# main.net
KiCad netlist of a schematic drawn in EAGLE
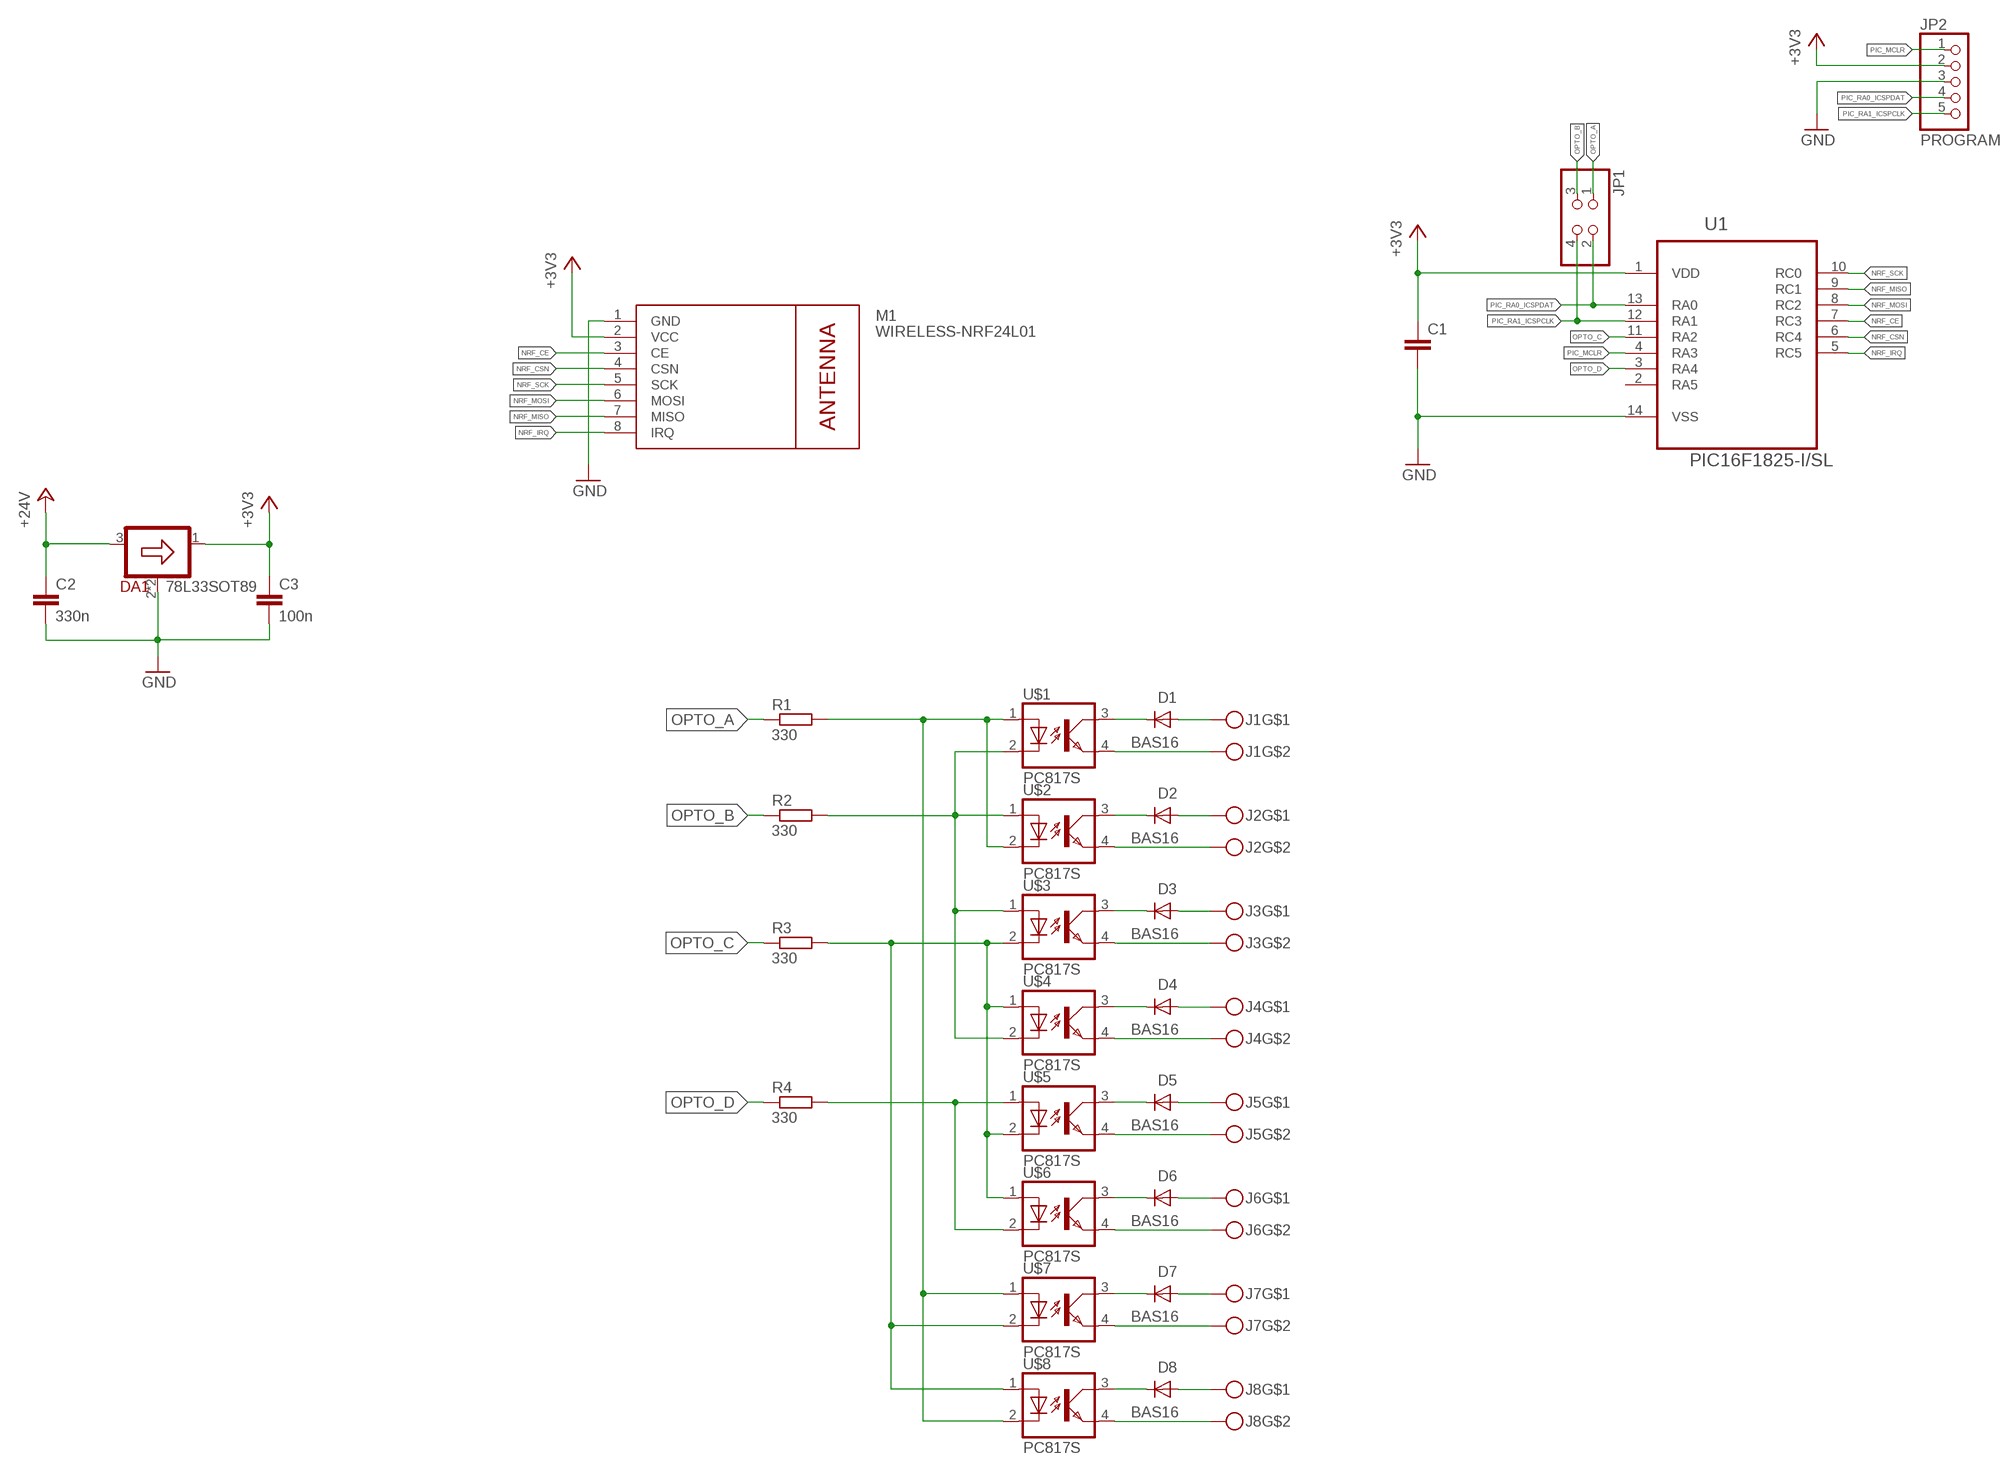
[diagram p0: schematic, sheet 1]

(export (version "E")
  (design (tool "Eeschema 10.0.6"))
  (components
    (comp (ref "C1")
      (value "C-EUC1206")
      (footprint "eagle-import:C1206")
      (libsource (lib "eagle-import") (part "C-EUC1206"))
    )
    (comp (ref "C2")
      (value "330n")
      (footprint "eagle-import:C1206")
      (libsource (lib "eagle-import") (part "C-EUC1206"))
    )
    (comp (ref "C3")
      (value "100n")
      (footprint "eagle-import:C1206")
      (libsource (lib "eagle-import") (part "C-EUC1206"))
    )
    (comp (ref "D1")
      (value "BAS16")
      (footprint "eagle-import:SOT23")
      (libsource (lib "eagle-import") (part "BAS16"))
    )
    (comp (ref "D2")
      (value "BAS16")
      (footprint "eagle-import:SOT23")
      (libsource (lib "eagle-import") (part "BAS16"))
    )
    (comp (ref "D3")
      (value "BAS16")
      (footprint "eagle-import:SOT23")
      (libsource (lib "eagle-import") (part "BAS16"))
    )
    (comp (ref "D4")
      (value "BAS16")
      (footprint "eagle-import:SOT23")
      (libsource (lib "eagle-import") (part "BAS16"))
    )
    (comp (ref "D5")
      (value "BAS16")
      (footprint "eagle-import:SOT23")
      (libsource (lib "eagle-import") (part "BAS16"))
    )
    (comp (ref "D6")
      (value "BAS16")
      (footprint "eagle-import:SOT23")
      (libsource (lib "eagle-import") (part "BAS16"))
    )
    (comp (ref "D7")
      (value "BAS16")
      (footprint "eagle-import:SOT23")
      (libsource (lib "eagle-import") (part "BAS16"))
    )
    (comp (ref "D8")
      (value "BAS16")
      (footprint "eagle-import:SOT23")
      (libsource (lib "eagle-import") (part "BAS16"))
    )
    (comp (ref "DA1")
      (value "78L33SOT89")
      (footprint "eagle-import:SOT89")
      (libsource (lib "eagle-import") (part "78L33SOT89"))
    )
    (comp (ref "J1")
      (value "SCREW-TERMINAL-2PIN")
      (footprint "eagle-import:PITCH4.3-PIN2")
      (libsource (lib "eagle-import") (part "SCREW-TERMINAL-2PIN"))
    )
    (comp (ref "J2")
      (value "SCREW-TERMINAL-2PIN")
      (footprint "eagle-import:PITCH4.3-PIN2")
      (libsource (lib "eagle-import") (part "SCREW-TERMINAL-2PIN"))
    )
    (comp (ref "J3")
      (value "SCREW-TERMINAL-2PIN")
      (footprint "eagle-import:PITCH4.3-PIN2")
      (libsource (lib "eagle-import") (part "SCREW-TERMINAL-2PIN"))
    )
    (comp (ref "J4")
      (value "SCREW-TERMINAL-2PIN")
      (footprint "eagle-import:PITCH4.3-PIN2")
      (libsource (lib "eagle-import") (part "SCREW-TERMINAL-2PIN"))
    )
    (comp (ref "J5")
      (value "SCREW-TERMINAL-2PIN")
      (footprint "eagle-import:PITCH4.3-PIN2")
      (libsource (lib "eagle-import") (part "SCREW-TERMINAL-2PIN"))
    )
    (comp (ref "J6")
      (value "SCREW-TERMINAL-2PIN")
      (footprint "eagle-import:PITCH4.3-PIN2")
      (libsource (lib "eagle-import") (part "SCREW-TERMINAL-2PIN"))
    )
    (comp (ref "J7")
      (value "SCREW-TERMINAL-2PIN")
      (footprint "eagle-import:PITCH4.3-PIN2")
      (libsource (lib "eagle-import") (part "SCREW-TERMINAL-2PIN"))
    )
    (comp (ref "J8")
      (value "SCREW-TERMINAL-2PIN")
      (footprint "eagle-import:PITCH4.3-PIN2")
      (libsource (lib "eagle-import") (part "SCREW-TERMINAL-2PIN"))
    )
    (comp (ref "JP1")
      (value "PINHD-2X2")
      (footprint "eagle-import:2X02")
      (libsource (lib "eagle-import") (part "PINHD-2X2"))
    )
    (comp (ref "JP2")
      (value "PROGRAM")
      (footprint "eagle-import:1X05")
      (libsource (lib "eagle-import") (part "PINHD-1X5"))
    )
    (comp (ref "M1")
      (value "WIRELESS-NRF24L01")
      (footprint "eagle-import:WIRELESS-NRF24L01")
      (libsource (lib "eagle-import") (part "WIRELESS-NRF24L01"))
    )
    (comp (ref "R1")
      (value "330")
      (footprint "eagle-import:R1206")
      (libsource (lib "eagle-import") (part "R-EU_R1206"))
    )
    (comp (ref "R2")
      (value "330")
      (footprint "eagle-import:R1206")
      (libsource (lib "eagle-import") (part "R-EU_R1206"))
    )
    (comp (ref "R3")
      (value "330")
      (footprint "eagle-import:R1206")
      (libsource (lib "eagle-import") (part "R-EU_R1206"))
    )
    (comp (ref "R4")
      (value "330")
      (footprint "eagle-import:R1206")
      (libsource (lib "eagle-import") (part "R-EU_R1206"))
    )
    (comp (ref "U$1")
      (value "PC817S")
      (footprint "eagle-import:SMD4-7")
      (libsource (lib "eagle-import") (part "PC817S"))
    )
    (comp (ref "U$2")
      (value "PC817S")
      (footprint "eagle-import:SMD4-7")
      (libsource (lib "eagle-import") (part "PC817S"))
    )
    (comp (ref "U$3")
      (value "PC817S")
      (footprint "eagle-import:SMD4-7")
      (libsource (lib "eagle-import") (part "PC817S"))
    )
    (comp (ref "U$4")
      (value "PC817S")
      (footprint "eagle-import:SMD4-7")
      (libsource (lib "eagle-import") (part "PC817S"))
    )
    (comp (ref "U$5")
      (value "PC817S")
      (footprint "eagle-import:SMD4-7")
      (libsource (lib "eagle-import") (part "PC817S"))
    )
    (comp (ref "U$6")
      (value "PC817S")
      (footprint "eagle-import:SMD4-7")
      (libsource (lib "eagle-import") (part "PC817S"))
    )
    (comp (ref "U$7")
      (value "PC817S")
      (footprint "eagle-import:SMD4-7")
      (libsource (lib "eagle-import") (part "PC817S"))
    )
    (comp (ref "U$8")
      (value "PC817S")
      (footprint "eagle-import:SMD4-7")
      (libsource (lib "eagle-import") (part "PC817S"))
    )
    (comp (ref "U1")
      (value "PIC16F1825-I/SL")
      (footprint "eagle-import:SOIC127P600X175-14N")
      (libsource (lib "eagle-import") (part "PIC16F1825-I/SL"))
    )
  )
  (nets
    (net (code "1") (name "+3V3") (class "Default")
      (node (ref "C1") (pin "1") (pinfunction "1_1") (pintype "passive"))
      (node (ref "C3") (pin "1") (pinfunction "1_1") (pintype "passive"))
      (node (ref "DA1") (pin "1") (pinfunction "OUT_1") (pintype "power_in"))
      (node (ref "JP2") (pin "2") (pinfunction "2_2") (pintype "passive"))
      (node (ref "M1") (pin "2") (pinfunction "VCC_2") (pintype "power_in"))
      (node (ref "U1") (pin "1") (pinfunction "VDD_1") (pintype "power_in"))
    )
    (net (code "2") (name "+24V") (class "Default")
      (node (ref "C2") (pin "1") (pinfunction "1_1") (pintype "passive"))
      (node (ref "DA1") (pin "3") (pinfunction "IN_3") (pintype "power_in"))
    )
    (net (code "3") (name "GND") (class "Default")
      (node (ref "C1") (pin "2") (pinfunction "2_2") (pintype "passive"))
      (node (ref "C2") (pin "2") (pinfunction "2_2") (pintype "passive"))
      (node (ref "C3") (pin "2") (pinfunction "2_2") (pintype "passive"))
      (node (ref "DA1") (pin "2") (pinfunction "GND_2") (pintype "power_in"))
      (node (ref "DA1") (pin "2@1") (pinfunction "GND_2@1") (pintype "power_in"))
      (node (ref "JP2") (pin "3") (pinfunction "3_3") (pintype "passive"))
      (node (ref "M1") (pin "1") (pinfunction "GND_1") (pintype "power_in"))
      (node (ref "U1") (pin "14") (pinfunction "VSS_14") (pintype "passive"))
    )
    (net (code "4") (name "NRF_CE") (class "Default")
      (node (ref "M1") (pin "3") (pinfunction "CE_3") (pintype "bidirectional"))
      (node (ref "U1") (pin "7") (pinfunction "RC3_7") (pintype "bidirectional"))
    )
    (net (code "5") (name "NRF_CSN") (class "Default")
      (node (ref "M1") (pin "4") (pinfunction "CSN_4") (pintype "bidirectional"))
      (node (ref "U1") (pin "6") (pinfunction "RC4_6") (pintype "bidirectional"))
    )
    (net (code "6") (name "NRF_IRQ") (class "Default")
      (node (ref "M1") (pin "8") (pinfunction "IRQ_8") (pintype "bidirectional"))
      (node (ref "U1") (pin "5") (pinfunction "RC5_5") (pintype "bidirectional"))
    )
    (net (code "7") (name "NRF_MISO") (class "Default")
      (node (ref "M1") (pin "7") (pinfunction "MISO_7") (pintype "bidirectional"))
      (node (ref "U1") (pin "9") (pinfunction "RC1_9") (pintype "bidirectional"))
    )
    (net (code "8") (name "NRF_MOSI") (class "Default")
      (node (ref "M1") (pin "6") (pinfunction "MOSI_6") (pintype "bidirectional"))
      (node (ref "U1") (pin "8") (pinfunction "RC2_8") (pintype "bidirectional"))
    )
    (net (code "9") (name "NRF_SCK") (class "Default")
      (node (ref "M1") (pin "5") (pinfunction "SCK_5") (pintype "bidirectional"))
      (node (ref "U1") (pin "10") (pinfunction "RC0_10") (pintype "bidirectional"))
    )
    (net (code "10") (name "Net-(D1-A)") (class "Default")
      (node (ref "D1") (pin "1") (pinfunction "A_1") (pintype "passive"))
      (node (ref "J1") (pin "1") (pinfunction "KL_1") (pintype "passive"))
    )
    (net (code "11") (name "Net-(D1-K)") (class "Default")
      (node (ref "D1") (pin "3") (pinfunction "K_3") (pintype "passive"))
      (node (ref "U$1") (pin "3") (pinfunction "COL_3") (pintype "passive"))
    )
    (net (code "12") (name "Net-(D2-A)") (class "Default")
      (node (ref "D2") (pin "1") (pinfunction "A_1") (pintype "passive"))
      (node (ref "J2") (pin "1") (pinfunction "KL_1") (pintype "passive"))
    )
    (net (code "13") (name "Net-(D2-K)") (class "Default")
      (node (ref "D2") (pin "3") (pinfunction "K_3") (pintype "passive"))
      (node (ref "U$2") (pin "3") (pinfunction "COL_3") (pintype "passive"))
    )
    (net (code "14") (name "Net-(D3-A)") (class "Default")
      (node (ref "D3") (pin "1") (pinfunction "A_1") (pintype "passive"))
      (node (ref "J3") (pin "1") (pinfunction "KL_1") (pintype "passive"))
    )
    (net (code "15") (name "Net-(D3-K)") (class "Default")
      (node (ref "D3") (pin "3") (pinfunction "K_3") (pintype "passive"))
      (node (ref "U$3") (pin "3") (pinfunction "COL_3") (pintype "passive"))
    )
    (net (code "16") (name "Net-(D4-A)") (class "Default")
      (node (ref "D4") (pin "1") (pinfunction "A_1") (pintype "passive"))
      (node (ref "J4") (pin "1") (pinfunction "KL_1") (pintype "passive"))
    )
    (net (code "17") (name "Net-(D4-K)") (class "Default")
      (node (ref "D4") (pin "3") (pinfunction "K_3") (pintype "passive"))
      (node (ref "U$4") (pin "3") (pinfunction "COL_3") (pintype "passive"))
    )
    (net (code "18") (name "Net-(D5-A)") (class "Default")
      (node (ref "D5") (pin "1") (pinfunction "A_1") (pintype "passive"))
      (node (ref "J5") (pin "1") (pinfunction "KL_1") (pintype "passive"))
    )
    (net (code "19") (name "Net-(D5-K)") (class "Default")
      (node (ref "D5") (pin "3") (pinfunction "K_3") (pintype "passive"))
      (node (ref "U$5") (pin "3") (pinfunction "COL_3") (pintype "passive"))
    )
    (net (code "20") (name "Net-(D6-A)") (class "Default")
      (node (ref "D6") (pin "1") (pinfunction "A_1") (pintype "passive"))
      (node (ref "J6") (pin "1") (pinfunction "KL_1") (pintype "passive"))
    )
    (net (code "21") (name "Net-(D6-K)") (class "Default")
      (node (ref "D6") (pin "3") (pinfunction "K_3") (pintype "passive"))
      (node (ref "U$6") (pin "3") (pinfunction "COL_3") (pintype "passive"))
    )
    (net (code "22") (name "Net-(D7-A)") (class "Default")
      (node (ref "D7") (pin "1") (pinfunction "A_1") (pintype "passive"))
      (node (ref "J7") (pin "1") (pinfunction "KL_1") (pintype "passive"))
    )
    (net (code "23") (name "Net-(D7-K)") (class "Default")
      (node (ref "D7") (pin "3") (pinfunction "K_3") (pintype "passive"))
      (node (ref "U$7") (pin "3") (pinfunction "COL_3") (pintype "passive"))
    )
    (net (code "24") (name "Net-(D8-A)") (class "Default")
      (node (ref "D8") (pin "1") (pinfunction "A_1") (pintype "passive"))
      (node (ref "J8") (pin "1") (pinfunction "KL_1") (pintype "passive"))
    )
    (net (code "25") (name "Net-(D8-K)") (class "Default")
      (node (ref "D8") (pin "3") (pinfunction "K_3") (pintype "passive"))
      (node (ref "U$8") (pin "3") (pinfunction "COL_3") (pintype "passive"))
    )
    (net (code "26") (name "Net-(J1B-KL)") (class "Default")
      (node (ref "J1") (pin "2") (pinfunction "KL_2") (pintype "passive"))
      (node (ref "U$1") (pin "4") (pinfunction "EMIT_4") (pintype "passive"))
    )
    (net (code "27") (name "Net-(J2B-KL)") (class "Default")
      (node (ref "J2") (pin "2") (pinfunction "KL_2") (pintype "passive"))
      (node (ref "U$2") (pin "4") (pinfunction "EMIT_4") (pintype "passive"))
    )
    (net (code "28") (name "Net-(J3B-KL)") (class "Default")
      (node (ref "J3") (pin "2") (pinfunction "KL_2") (pintype "passive"))
      (node (ref "U$3") (pin "4") (pinfunction "EMIT_4") (pintype "passive"))
    )
    (net (code "29") (name "Net-(J4B-KL)") (class "Default")
      (node (ref "J4") (pin "2") (pinfunction "KL_2") (pintype "passive"))
      (node (ref "U$4") (pin "4") (pinfunction "EMIT_4") (pintype "passive"))
    )
    (net (code "30") (name "Net-(J5B-KL)") (class "Default")
      (node (ref "J5") (pin "2") (pinfunction "KL_2") (pintype "passive"))
      (node (ref "U$5") (pin "4") (pinfunction "EMIT_4") (pintype "passive"))
    )
    (net (code "31") (name "Net-(J6B-KL)") (class "Default")
      (node (ref "J6") (pin "2") (pinfunction "KL_2") (pintype "passive"))
      (node (ref "U$6") (pin "4") (pinfunction "EMIT_4") (pintype "passive"))
    )
    (net (code "32") (name "Net-(J7B-KL)") (class "Default")
      (node (ref "J7") (pin "2") (pinfunction "KL_2") (pintype "passive"))
      (node (ref "U$7") (pin "4") (pinfunction "EMIT_4") (pintype "passive"))
    )
    (net (code "33") (name "Net-(J8B-KL)") (class "Default")
      (node (ref "J8") (pin "2") (pinfunction "KL_2") (pintype "passive"))
      (node (ref "U$8") (pin "4") (pinfunction "EMIT_4") (pintype "passive"))
    )
    (net (code "34") (name "Net-(U$1-A)") (class "Default")
      (node (ref "R1") (pin "2") (pinfunction "2_2") (pintype "passive"))
      (node (ref "U$1") (pin "1") (pinfunction "A_1") (pintype "passive"))
      (node (ref "U$2") (pin "2") (pinfunction "C_2") (pintype "passive"))
      (node (ref "U$7") (pin "1") (pinfunction "A_1") (pintype "passive"))
      (node (ref "U$8") (pin "2") (pinfunction "C_2") (pintype "passive"))
    )
    (net (code "35") (name "Net-(U$1-C)") (class "Default")
      (node (ref "R2") (pin "2") (pinfunction "2_2") (pintype "passive"))
      (node (ref "U$1") (pin "2") (pinfunction "C_2") (pintype "passive"))
      (node (ref "U$2") (pin "1") (pinfunction "A_1") (pintype "passive"))
      (node (ref "U$3") (pin "1") (pinfunction "A_1") (pintype "passive"))
      (node (ref "U$4") (pin "2") (pinfunction "C_2") (pintype "passive"))
    )
    (net (code "36") (name "Net-(U$3-C)") (class "Default")
      (node (ref "R3") (pin "2") (pinfunction "2_2") (pintype "passive"))
      (node (ref "U$3") (pin "2") (pinfunction "C_2") (pintype "passive"))
      (node (ref "U$4") (pin "1") (pinfunction "A_1") (pintype "passive"))
      (node (ref "U$5") (pin "2") (pinfunction "C_2") (pintype "passive"))
      (node (ref "U$6") (pin "1") (pinfunction "A_1") (pintype "passive"))
      (node (ref "U$7") (pin "2") (pinfunction "C_2") (pintype "passive"))
      (node (ref "U$8") (pin "1") (pinfunction "A_1") (pintype "passive"))
    )
    (net (code "37") (name "Net-(U$5-A)") (class "Default")
      (node (ref "R4") (pin "2") (pinfunction "2_2") (pintype "passive"))
      (node (ref "U$5") (pin "1") (pinfunction "A_1") (pintype "passive"))
      (node (ref "U$6") (pin "2") (pinfunction "C_2") (pintype "passive"))
    )
    (net (code "38") (name "OPTO_A") (class "Default")
      (node (ref "JP1") (pin "1") (pinfunction "1_1") (pintype "passive"))
      (node (ref "R1") (pin "1") (pinfunction "1_1") (pintype "passive"))
    )
    (net (code "39") (name "OPTO_B") (class "Default")
      (node (ref "JP1") (pin "3") (pinfunction "3_3") (pintype "passive"))
      (node (ref "R2") (pin "1") (pinfunction "1_1") (pintype "passive"))
    )
    (net (code "40") (name "OPTO_C") (class "Default")
      (node (ref "R3") (pin "1") (pinfunction "1_1") (pintype "passive"))
      (node (ref "U1") (pin "11") (pinfunction "RA2_11") (pintype "bidirectional"))
    )
    (net (code "41") (name "OPTO_D") (class "Default")
      (node (ref "R4") (pin "1") (pinfunction "1_1") (pintype "passive"))
      (node (ref "U1") (pin "3") (pinfunction "RA4_3") (pintype "bidirectional"))
    )
    (net (code "42") (name "PIC_MCLR") (class "Default")
      (node (ref "JP2") (pin "1") (pinfunction "1_1") (pintype "passive"))
      (node (ref "U1") (pin "4") (pinfunction "RA3_4") (pintype "input"))
    )
    (net (code "43") (name "PIC_RA0_ICSPDAT") (class "Default")
      (node (ref "JP1") (pin "2") (pinfunction "2_2") (pintype "passive"))
      (node (ref "JP2") (pin "4") (pinfunction "4_4") (pintype "passive"))
      (node (ref "U1") (pin "13") (pinfunction "RA0_13") (pintype "bidirectional"))
    )
    (net (code "44") (name "PIC_RA1_ICSPCLK") (class "Default")
      (node (ref "JP1") (pin "4") (pinfunction "4_4") (pintype "passive"))
      (node (ref "JP2") (pin "5") (pinfunction "5_5") (pintype "passive"))
      (node (ref "U1") (pin "12") (pinfunction "RA1_12") (pintype "bidirectional"))
    )
    (net (code "45") (name "unconnected-(U1-RA5-Pad2)") (class "Default")
      (node (ref "U1") (pin "2") (pinfunction "RA5_2") (pintype "bidirectional"))
    )
  )
)
